# NewBee.net
KiCad netlist of a schematic drawn in Altium Designer
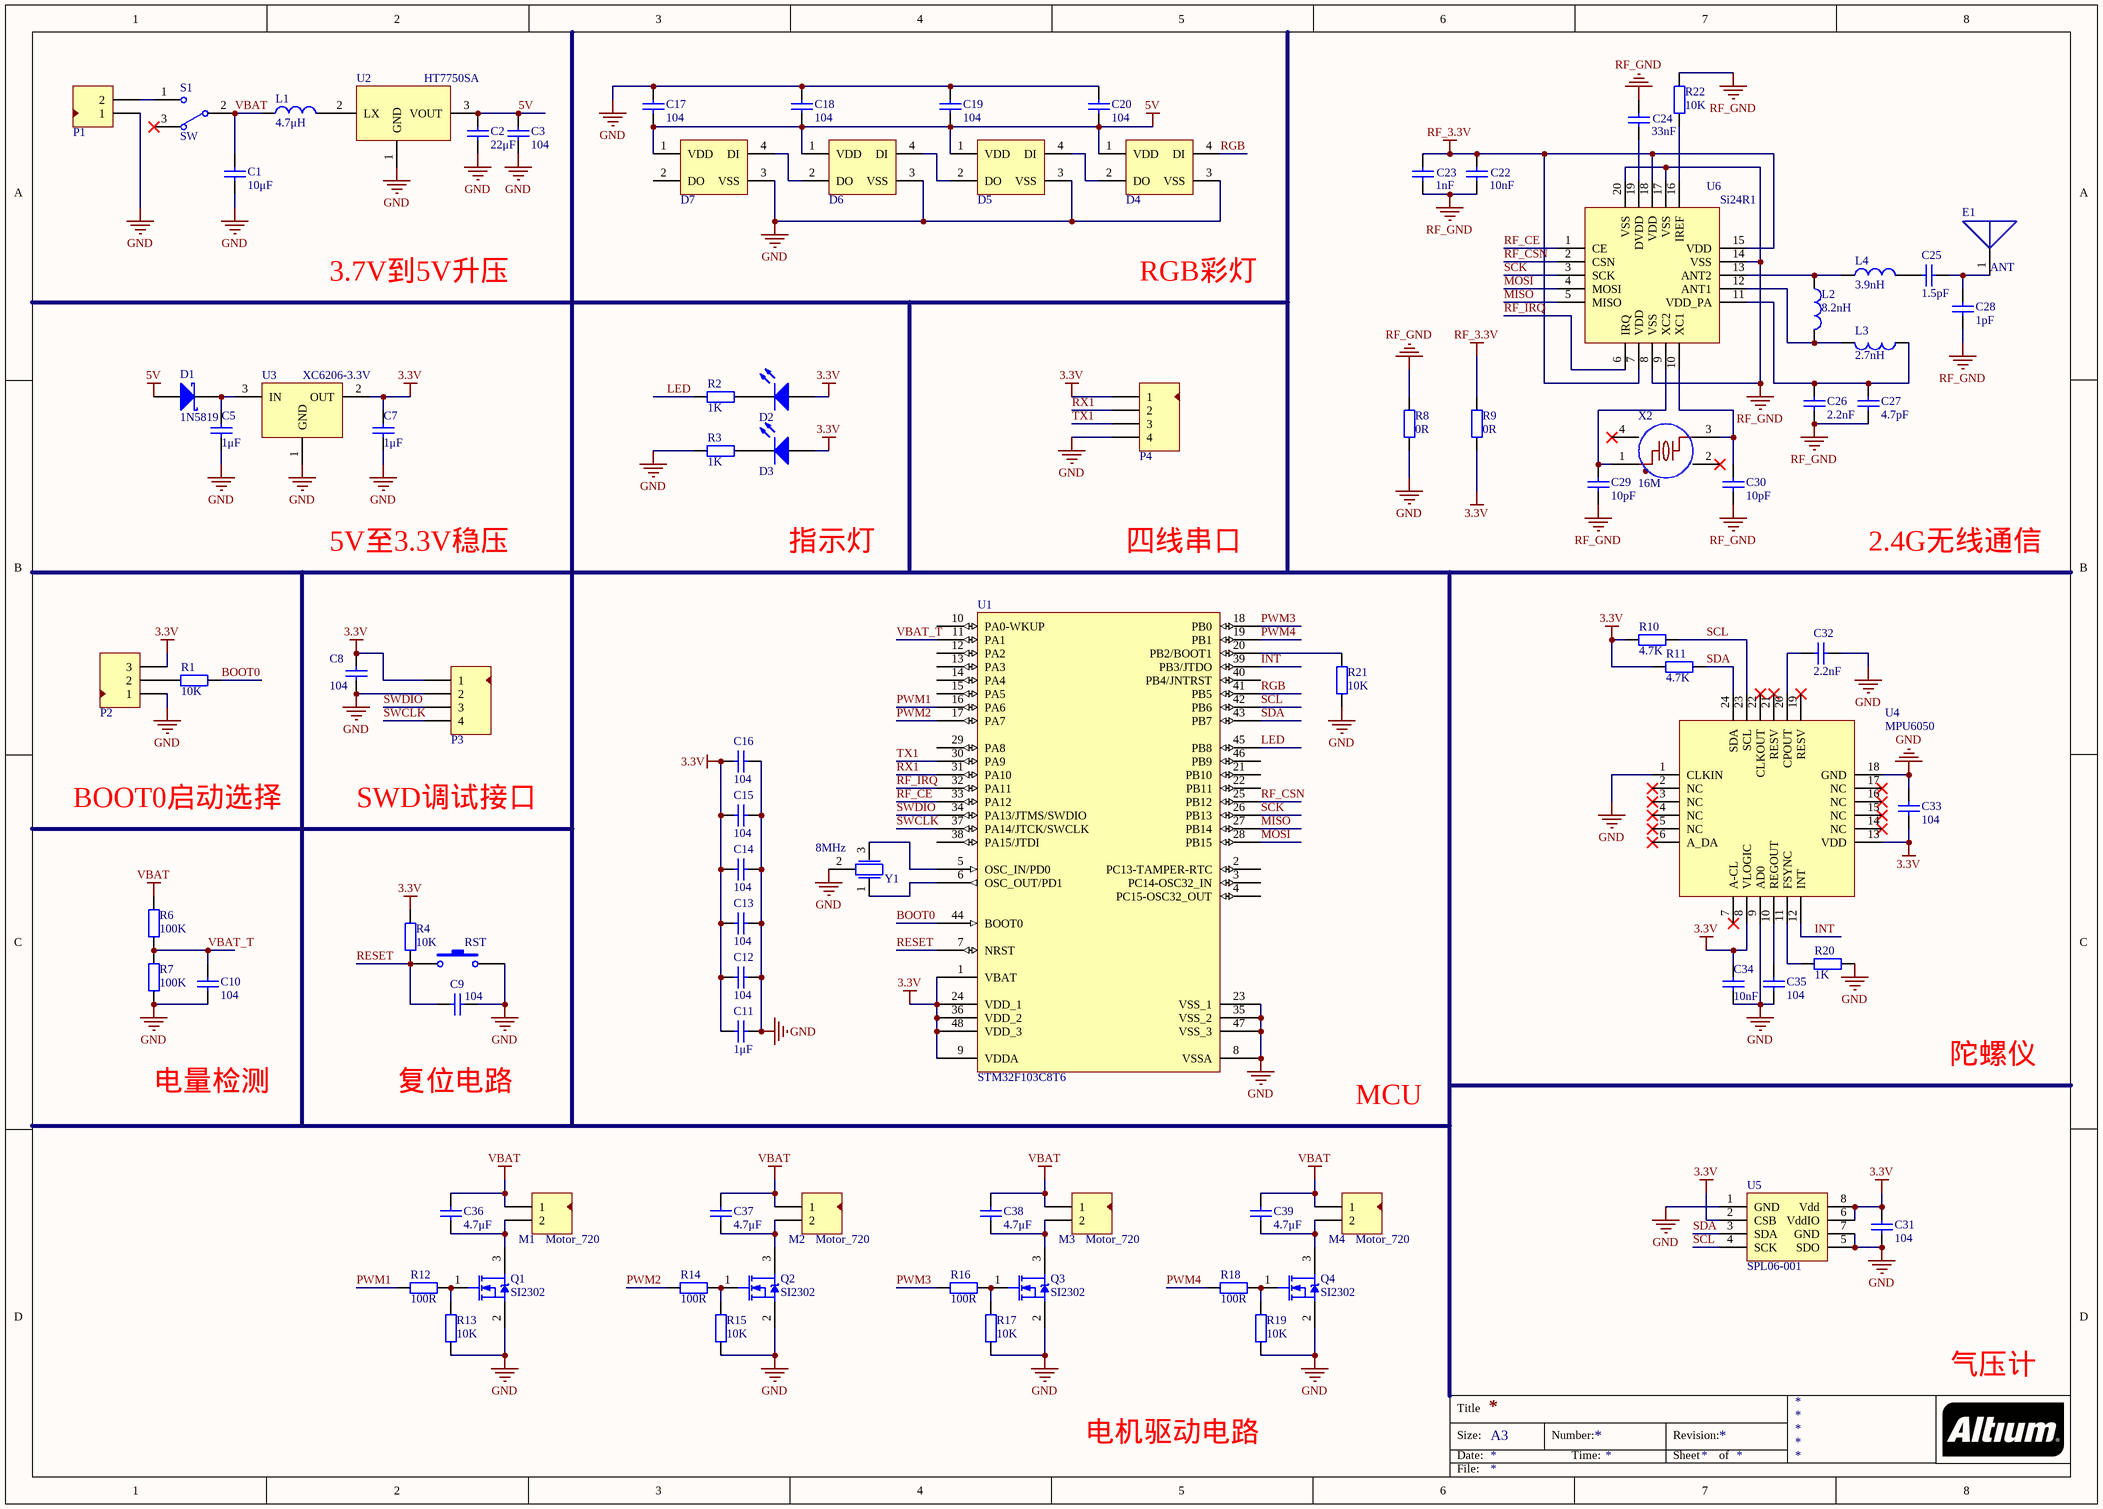
[diagram p0: NewBee.SchDoc]

(export (version "E")
  (design (tool "Eeschema 10.0.6"))
  (components
    (comp (ref "C1")
      (value "10μF")
      (footprint "C-0603")
      (description "贴片瓷片电容")
      (fields (field (name "PUBLISHER") "Altium Limited"))
      (libsource (lib "ChunLee") (part "Cap-S"))
    )
    (comp (ref "C2")
      (value "22μF")
      (footprint "C-0603")
      (description "贴片瓷片电容")
      (fields (field (name "PUBLISHER") "Altium Limited"))
      (libsource (lib "ChunLee") (part "Cap-S"))
    )
    (comp (ref "C3")
      (value "104")
      (footprint "C-0603")
      (description "贴片瓷片电容")
      (fields (field (name "PUBLISHER") "Altium Limited"))
      (libsource (lib "ChunLee") (part "Cap-S"))
    )
    (comp (ref "C5")
      (value "1μF")
      (footprint "C-0603")
      (description "贴片瓷片电容")
      (fields (field (name "PUBLISHER") "Altium Limited"))
      (libsource (lib "ChunLee") (part "Cap-S"))
    )
    (comp (ref "C7")
      (value "1μF")
      (footprint "C-0603")
      (description "贴片瓷片电容")
      (fields (field (name "PUBLISHER") "Altium Limited"))
      (libsource (lib "ChunLee") (part "Cap-S"))
    )
    (comp (ref "C8")
      (value "104")
      (footprint "C-0603")
      (description "贴片瓷片电容")
      (fields (field (name "PUBLISHER") "Altium Limited"))
      (libsource (lib "ChunLee") (part "Cap-S"))
    )
    (comp (ref "C9")
      (value "104")
      (footprint "C-0603")
      (description "贴片瓷片电容")
      (fields (field (name "PUBLISHER") "Altium Limited"))
      (libsource (lib "ChunLee") (part "Cap-S"))
    )
    (comp (ref "C10")
      (value "104")
      (footprint "C-0603")
      (description "贴片瓷片电容")
      (fields (field (name "PUBLISHER") "Altium Limited"))
      (libsource (lib "ChunLee") (part "Cap-S"))
    )
    (comp (ref "C11")
      (value "1μF")
      (footprint "C-0603")
      (description "贴片瓷片电容")
      (fields (field (name "PUBLISHER") "Altium Limited"))
      (libsource (lib "ChunLee") (part "Cap-S"))
    )
    (comp (ref "C12")
      (value "104")
      (footprint "C-0603")
      (description "贴片瓷片电容")
      (fields (field (name "PUBLISHER") "Altium Limited"))
      (libsource (lib "ChunLee") (part "Cap-S"))
    )
    (comp (ref "C13")
      (value "104")
      (footprint "C-0603")
      (description "贴片瓷片电容")
      (fields (field (name "PUBLISHER") "Altium Limited"))
      (libsource (lib "ChunLee") (part "Cap-S"))
    )
    (comp (ref "C14")
      (value "104")
      (footprint "C-0603")
      (description "贴片瓷片电容")
      (fields (field (name "PUBLISHER") "Altium Limited"))
      (libsource (lib "ChunLee") (part "Cap-S"))
    )
    (comp (ref "C15")
      (value "104")
      (footprint "C-0603")
      (description "贴片瓷片电容")
      (fields (field (name "PUBLISHER") "Altium Limited"))
      (libsource (lib "ChunLee") (part "Cap-S"))
    )
    (comp (ref "C16")
      (value "104")
      (footprint "C-0603")
      (description "贴片瓷片电容")
      (fields (field (name "PUBLISHER") "Altium Limited"))
      (libsource (lib "ChunLee") (part "Cap-S"))
    )
    (comp (ref "C17")
      (value "104")
      (footprint "C-0603")
      (description "贴片瓷片电容")
      (fields (field (name "PUBLISHER") "Altium Limited"))
      (libsource (lib "ChunLee") (part "Cap-S"))
    )
    (comp (ref "C18")
      (value "104")
      (footprint "C-0603")
      (description "贴片瓷片电容")
      (fields (field (name "PUBLISHER") "Altium Limited"))
      (libsource (lib "ChunLee") (part "Cap-S"))
    )
    (comp (ref "C19")
      (value "104")
      (footprint "C-0603")
      (description "贴片瓷片电容")
      (fields (field (name "PUBLISHER") "Altium Limited"))
      (libsource (lib "ChunLee") (part "Cap-S"))
    )
    (comp (ref "C20")
      (value "104")
      (footprint "C-0603")
      (description "贴片瓷片电容")
      (fields (field (name "PUBLISHER") "Altium Limited"))
      (libsource (lib "ChunLee") (part "Cap-S"))
    )
    (comp (ref "C22")
      (value "10nF")
      (footprint "C-0603")
      (description "贴片瓷片电容")
      (fields (field (name "PUBLISHER") "Altium Limited"))
      (libsource (lib "ChunLee") (part "Cap-S"))
    )
    (comp (ref "C23")
      (value "1nF")
      (footprint "C-0603")
      (description "贴片瓷片电容")
      (fields (field (name "PUBLISHER") "Altium Limited"))
      (libsource (lib "ChunLee") (part "Cap-S"))
    )
    (comp (ref "C24")
      (value "33nF")
      (footprint "C-0603")
      (description "贴片瓷片电容")
      (fields (field (name "PUBLISHER") "Altium Limited"))
      (libsource (lib "ChunLee") (part "Cap-S"))
    )
    (comp (ref "C25")
      (value "1.5pF")
      (footprint "C-0603")
      (description "贴片瓷片电容")
      (fields (field (name "PUBLISHER") "Altium Limited"))
      (libsource (lib "ChunLee") (part "Cap-S"))
    )
    (comp (ref "C26")
      (value "2.2nF")
      (footprint "C-0603")
      (description "贴片瓷片电容")
      (fields (field (name "PUBLISHER") "Altium Limited"))
      (libsource (lib "ChunLee") (part "Cap-S"))
    )
    (comp (ref "C27")
      (value "4.7pF")
      (footprint "C-0603")
      (description "贴片瓷片电容")
      (fields (field (name "PUBLISHER") "Altium Limited"))
      (libsource (lib "ChunLee") (part "Cap-S"))
    )
    (comp (ref "C28")
      (value "1pF")
      (footprint "C-0603")
      (description "贴片瓷片电容")
      (fields (field (name "PUBLISHER") "Altium Limited"))
      (libsource (lib "ChunLee") (part "Cap-S"))
    )
    (comp (ref "C29")
      (value "10pF")
      (footprint "C-0603")
      (description "贴片瓷片电容")
      (fields (field (name "PUBLISHER") "Altium Limited"))
      (libsource (lib "ChunLee") (part "Cap-S"))
    )
    (comp (ref "C30")
      (value "10pF")
      (footprint "C-0603")
      (description "贴片瓷片电容")
      (fields (field (name "PUBLISHER") "Altium Limited"))
      (libsource (lib "ChunLee") (part "Cap-S"))
    )
    (comp (ref "C31")
      (value "104")
      (footprint "C-0603")
      (description "贴片瓷片电容")
      (fields (field (name "PUBLISHER") "Altium Limited"))
      (libsource (lib "ChunLee") (part "Cap-S"))
    )
    (comp (ref "C32")
      (value "2.2nF")
      (footprint "C-0603")
      (description "贴片瓷片电容")
      (fields (field (name "PUBLISHER") "Altium Limited"))
      (libsource (lib "ChunLee") (part "Cap-S"))
    )
    (comp (ref "C33")
      (value "104")
      (footprint "C-0603")
      (description "贴片瓷片电容")
      (fields (field (name "PUBLISHER") "Altium Limited"))
      (libsource (lib "ChunLee") (part "Cap-S"))
    )
    (comp (ref "C34")
      (value "10nF")
      (footprint "C-0603")
      (description "贴片瓷片电容")
      (fields (field (name "PUBLISHER") "Altium Limited"))
      (libsource (lib "ChunLee") (part "Cap-S"))
    )
    (comp (ref "C35")
      (value "104")
      (footprint "C-0603")
      (description "贴片瓷片电容")
      (fields (field (name "PUBLISHER") "Altium Limited"))
      (libsource (lib "ChunLee") (part "Cap-S"))
    )
    (comp (ref "C36")
      (value "4.7μF")
      (footprint "C-0603")
      (description "贴片瓷片电容")
      (fields (field (name "PUBLISHER") "Altium Limited"))
      (libsource (lib "ChunLee") (part "Cap-S"))
    )
    (comp (ref "C37")
      (value "4.7μF")
      (footprint "C-0603")
      (description "贴片瓷片电容")
      (fields (field (name "PUBLISHER") "Altium Limited"))
      (libsource (lib "ChunLee") (part "Cap-S"))
    )
    (comp (ref "C38")
      (value "4.7μF")
      (footprint "C-0603")
      (description "贴片瓷片电容")
      (fields (field (name "PUBLISHER") "Altium Limited"))
      (libsource (lib "ChunLee") (part "Cap-S"))
    )
    (comp (ref "C39")
      (value "4.7μF")
      (footprint "C-0603")
      (description "贴片瓷片电容")
      (fields (field (name "PUBLISHER") "Altium Limited"))
      (libsource (lib "ChunLee") (part "Cap-S"))
    )
    (comp (ref "D1")
      (value "1N5819")
      (footprint "SOD-323_L1.6-W1.3-LS2.7-RD")
      (description "肖特基二极管")
      (fields (field (name "TYPE") "1N5819") (field (name "PUBLISHER") "Altium Limited"))
      (libsource (lib "ChunLee") (part "Diode-Schottky"))
    )
    (comp (ref "D2")
      (value "LED0")
      (footprint "LED-0805")
      (description "发光二极管")
      (fields (field (name "PUBLISHER") "Altium Limited"))
      (libsource (lib "ChunLee") (part "LED0"))
    )
    (comp (ref "D3")
      (value "LED0")
      (footprint "LED-0805")
      (description "发光二极管")
      (fields (field (name "PUBLISHER") "Altium Limited"))
      (libsource (lib "ChunLee") (part "LED0"))
    )
    (comp (ref "D4")
      (value "WS2812B")
      (footprint "SMD-5050-4")
      (description "WS2812B 4脚RGB全彩LED")
      (libsource (lib "ChunLee") (part "WS2812B"))
    )
    (comp (ref "D5")
      (value "WS2812B")
      (footprint "SMD-5050-4")
      (description "WS2812B 4脚RGB全彩LED")
      (libsource (lib "ChunLee") (part "WS2812B"))
    )
    (comp (ref "D6")
      (value "WS2812B")
      (footprint "SMD-5050-4")
      (description "WS2812B 4脚RGB全彩LED")
      (libsource (lib "ChunLee") (part "WS2812B"))
    )
    (comp (ref "D7")
      (value "WS2812B")
      (footprint "SMD-5050-4")
      (description "WS2812B 4脚RGB全彩LED")
      (libsource (lib "ChunLee") (part "WS2812B"))
    )
    (comp (ref "E1")
      (value "ANT")
      (footprint "NewBee_PcbLib:AN3216")
      (description "2.4G Antenna")
      (fields (field (name "PUBLISHER") "mazhongwei"))
      (libsource (lib "NewBee_Schlib") (part "ANT"))
    )
    (comp (ref "L1")
      (value "4.7μH")
      (footprint "1210")
      (description "电感")
      (fields (field (name "Comment") "Inductor") (field (name "PUBLISHER") "Altium Limited"))
      (libsource (lib "ChunLee") (part "Inductor"))
    )
    (comp (ref "L2")
      (value "8.2nH")
      (footprint "0603-1")
      (description "电感")
      (fields (field (name "Comment") "Inductor") (field (name "PUBLISHER") "Altium Limited"))
      (libsource (lib "ChunLee") (part "Inductor"))
    )
    (comp (ref "L3")
      (value "2.7nH")
      (footprint "0603-1")
      (description "电感")
      (fields (field (name "Comment") "Inductor") (field (name "PUBLISHER") "Altium Limited"))
      (libsource (lib "ChunLee") (part "Inductor"))
    )
    (comp (ref "L4")
      (value "3.9nH")
      (footprint "0603-1")
      (description "电感")
      (fields (field (name "Comment") "Inductor") (field (name "PUBLISHER") "Altium Limited"))
      (libsource (lib "ChunLee") (part "Inductor"))
    )
    (comp (ref "M1")
      (value "Motor_720")
      (footprint "PH2.0-2P-TH")
      (description "接插件")
      (fields (field (name "PUBLISHER") "Altium Limited"))
      (libsource (lib "HDR_ChunLee") (part "Header 2"))
    )
    (comp (ref "M2")
      (value "Motor_720")
      (footprint "PH2.0-2P-TH")
      (description "接插件")
      (fields (field (name "PUBLISHER") "Altium Limited"))
      (libsource (lib "HDR_ChunLee") (part "Header 2"))
    )
    (comp (ref "M3")
      (value "Motor_720")
      (footprint "PH2.0-2P-TH")
      (description "接插件")
      (fields (field (name "PUBLISHER") "Altium Limited"))
      (libsource (lib "HDR_ChunLee") (part "Header 2"))
    )
    (comp (ref "M4")
      (value "Motor_720")
      (footprint "PH2.0-2P-TH")
      (description "接插件")
      (fields (field (name "PUBLISHER") "Altium Limited"))
      (libsource (lib "HDR_ChunLee") (part "Header 2"))
    )
    (comp (ref "P1")
      (value "Header 2")
      (footprint "PH2.0-2P-SMD-WT")
      (description "接插件")
      (fields (field (name "PUBLISHER") "Altium Limited"))
      (libsource (lib "") (part "Header 2_1"))
    )
    (comp (ref "P2")
      (value "Header 3")
      (footprint "HDR3X1-2.54")
      (description "接插件")
      (fields (field (name "PUBLISHER") "Altium Limited"))
      (libsource (lib "HDR_ChunLee") (part "Header 3"))
    )
    (comp (ref "P3")
      (value "Header 4")
      (footprint "HDR4X1-2.54")
      (description "接插件")
      (fields (field (name "PUBLISHER") "Altium Limited"))
      (libsource (lib "HDR_ChunLee") (part "Header 4"))
    )
    (comp (ref "P4")
      (value "Header 4")
      (footprint "HDR4X1-2.54")
      (description "接插件")
      (fields (field (name "PUBLISHER") "Altium Limited"))
      (libsource (lib "HDR_ChunLee") (part "Header 4"))
    )
    (comp (ref "Q1")
      (value "SI2302")
      (footprint "SOT23-3")
      (description "N沟道贴片")
      (fields (field (name "PUBLISHER") "Altium Limited"))
      (libsource (lib "ChunLee") (part "SI2302"))
    )
    (comp (ref "Q2")
      (value "SI2302")
      (footprint "SOT23-3")
      (description "N沟道贴片")
      (fields (field (name "PUBLISHER") "Altium Limited"))
      (libsource (lib "ChunLee") (part "SI2302"))
    )
    (comp (ref "Q3")
      (value "SI2302")
      (footprint "SOT23-3")
      (description "N沟道贴片")
      (fields (field (name "PUBLISHER") "Altium Limited"))
      (libsource (lib "ChunLee") (part "SI2302"))
    )
    (comp (ref "Q4")
      (value "SI2302")
      (footprint "SOT23-3")
      (description "N沟道贴片")
      (fields (field (name "PUBLISHER") "Altium Limited"))
      (libsource (lib "ChunLee") (part "SI2302"))
    )
    (comp (ref "R1")
      (value "10K")
      (footprint "0603-1")
      (description "贴片电阻")
      (fields (field (name "PUBLISHER") "Altium Limited"))
      (libsource (lib "") (part "Res1_3"))
    )
    (comp (ref "R2")
      (value "1K")
      (footprint "0603-1")
      (description "贴片电阻")
      (fields (field (name "PUBLISHER") "Altium Limited"))
      (libsource (lib "") (part "Res1_2"))
    )
    (comp (ref "R3")
      (value "1K")
      (footprint "0603-1")
      (description "贴片电阻")
      (fields (field (name "PUBLISHER") "Altium Limited"))
      (libsource (lib "") (part "Res1_2"))
    )
    (comp (ref "R4")
      (value "10K")
      (footprint "0603-1")
      (description "贴片电阻")
      (fields (field (name "PUBLISHER") "Altium Limited"))
      (libsource (lib "") (part "Res1_1"))
    )
    (comp (ref "R6")
      (value "100K")
      (footprint "0603-1")
      (description "贴片电阻")
      (fields (field (name "PUBLISHER") "Altium Limited"))
      (libsource (lib "ChunLee") (part "Res1"))
    )
    (comp (ref "R7")
      (value "100K")
      (footprint "0603-1")
      (description "贴片电阻")
      (fields (field (name "PUBLISHER") "Altium Limited"))
      (libsource (lib "ChunLee") (part "Res1"))
    )
    (comp (ref "R8")
      (value "0R")
      (footprint "0603-1")
      (description "贴片电阻")
      (fields (field (name "PUBLISHER") "Altium Limited"))
      (libsource (lib "ChunLee") (part "Res1"))
    )
    (comp (ref "R9")
      (value "0R")
      (footprint "0603-1")
      (description "贴片电阻")
      (fields (field (name "PUBLISHER") "Altium Limited"))
      (libsource (lib "ChunLee") (part "Res1"))
    )
    (comp (ref "R10")
      (value "4.7K")
      (footprint "0603-1")
      (description "贴片电阻")
      (fields (field (name "PUBLISHER") "Altium Limited"))
      (libsource (lib "") (part "Res1_2"))
    )
    (comp (ref "R11")
      (value "4.7K")
      (footprint "0603-1")
      (description "贴片电阻")
      (fields (field (name "PUBLISHER") "Altium Limited"))
      (libsource (lib "") (part "Res1_2"))
    )
    (comp (ref "R12")
      (value "100R")
      (footprint "0603-1")
      (description "贴片电阻")
      (fields (field (name "PUBLISHER") "Altium Limited"))
      (libsource (lib "") (part "Res1_2"))
    )
    (comp (ref "R13")
      (value "10K")
      (footprint "0603-1")
      (description "贴片电阻")
      (fields (field (name "PUBLISHER") "Altium Limited"))
      (libsource (lib "") (part "Res1_1"))
    )
    (comp (ref "R14")
      (value "100R")
      (footprint "0603-1")
      (description "贴片电阻")
      (fields (field (name "PUBLISHER") "Altium Limited"))
      (libsource (lib "") (part "Res1_2"))
    )
    (comp (ref "R15")
      (value "10K")
      (footprint "0603-1")
      (description "贴片电阻")
      (fields (field (name "PUBLISHER") "Altium Limited"))
      (libsource (lib "") (part "Res1_1"))
    )
    (comp (ref "R16")
      (value "100R")
      (footprint "0603-1")
      (description "贴片电阻")
      (fields (field (name "PUBLISHER") "Altium Limited"))
      (libsource (lib "") (part "Res1_2"))
    )
    (comp (ref "R17")
      (value "10K")
      (footprint "0603-1")
      (description "贴片电阻")
      (fields (field (name "PUBLISHER") "Altium Limited"))
      (libsource (lib "") (part "Res1_1"))
    )
    (comp (ref "R18")
      (value "100R")
      (footprint "0603-1")
      (description "贴片电阻")
      (fields (field (name "PUBLISHER") "Altium Limited"))
      (libsource (lib "") (part "Res1_2"))
    )
    (comp (ref "R19")
      (value "10K")
      (footprint "0603-1")
      (description "贴片电阻")
      (fields (field (name "PUBLISHER") "Altium Limited"))
      (libsource (lib "") (part "Res1_1"))
    )
    (comp (ref "R20")
      (value "1K")
      (footprint "0603-1")
      (description "贴片电阻")
      (fields (field (name "PUBLISHER") "Altium Limited"))
      (libsource (lib "") (part "Res1_3"))
    )
    (comp (ref "R21")
      (value "10K")
      (footprint "0603-1")
      (description "贴片电阻")
      (fields (field (name "PUBLISHER") "Altium Limited"))
      (libsource (lib "ChunLee") (part "Res1"))
    )
    (comp (ref "R22")
      (value "10K")
      (footprint "0603-1")
      (description "贴片电阻")
      (fields (field (name "PUBLISHER") "Altium Limited"))
      (libsource (lib "ChunLee") (part "Res1"))
    )
    (comp (ref "RST")
      (value "SW-PB")
      (footprint "SW-SMD_L4.0-W3.0-P4.8-LS5.0-L")
      (description "微动开关")
      (fields (field (name "PUBLISHER") "Altium Limited"))
      (libsource (lib "ChunLee") (part "SW-PB"))
    )
    (comp (ref "S1")
      (value "SW")
      (footprint "SW-SMD_DEALON_MK-12D04-G2")
      (description "开关")
      (fields (field (name "PUBLISHER") "Altium Limited"))
      (libsource (lib "ChunLee") (part "SW-SPDT"))
    )
    (comp (ref "U1")
      (value "STM32F103C8T6")
      (footprint "LQFP-48")
      (description "STM32F103, 48引脚, 64Kb Flash, 20Kb SRAM")
      (fields (field (name "PUBLISHER") "Altium Limited"))
      (libsource (lib "ChunLee") (part "STM32F103C8T6"))
    )
    (comp (ref "U2")
      (value "HT7750SA")
      (footprint "SOT23-3")
      (libsource (lib "ChunLee") (part "HT7750SA_3pins"))
    )
    (comp (ref "U3")
      (value "XC6206-3.3V")
      (footprint "SOT23-3")
      (description "稳压芯片")
      (libsource (lib "ChunLee") (part "XC6206"))
    )
    (comp (ref "U4") (value "MPU6050") (footprint "QFN-24") (libsource (lib "ChunLee") (part "MPU6050")))
    (comp (ref "U5")
      (value "SPL06-001")
      (footprint "SENSOR-SMD_SPL06-001")
      (description "气压计")
      (fields (field (name "PUBLISHER") "mazhongwei"))
      (libsource (lib "NewBee_Schlib") (part "FBM320"))
    )
    (comp (ref "U6") (value "Si24R1") (footprint "QFN20") (libsource (lib "NewBee_Schlib") (part "nRF24L01")))
    (comp (ref "X2")
      (value "16M")
      (footprint "X-SMD_4P-L3.2-W2.5-BL")
      (libsource (lib "ChunLee") (part "XTAL-4PIN"))
    )
    (comp (ref "Y1")
      (value "8MHz")
      (footprint "OSC-SMD_3P-L3.2-W1.3-P1.20-L")
      (description "贴片晶振")
      (libsource (lib "ChunLee") (part "XTAL-3PIN"))
    )
  )
  (nets
    (net (code "1") (name "/BOOT0") (class "Default")
      (node (ref "R1") (pin "1") (pinfunction "1_1") (pintype "passive"))
      (node (ref "U1") (pin "44") (pinfunction "BOOT0_44") (pintype "input"))
    )
    (net (code "2") (name "/INT") (class "Default")
      (node (ref "U1") (pin "39") (pinfunction "PB3/JTDO_39") (pintype "bidirectional"))
      (node (ref "U4") (pin "12") (pinfunction "INT_12") (pintype "passive"))
    )
    (net (code "3") (name "/LED") (class "Default")
      (node (ref "R2") (pin "1") (pinfunction "1_1") (pintype "passive"))
      (node (ref "U1") (pin "45") (pinfunction "PB8_45") (pintype "bidirectional"))
    )
    (net (code "4") (name "/MISO") (class "Default")
      (node (ref "U1") (pin "27") (pinfunction "PB14_27") (pintype "bidirectional"))
      (node (ref "U6") (pin "5") (pinfunction "MISO_5") (pintype "passive"))
    )
    (net (code "5") (name "/MOSI") (class "Default")
      (node (ref "U1") (pin "28") (pinfunction "PB15_28") (pintype "bidirectional"))
      (node (ref "U6") (pin "4") (pinfunction "MOSI_4") (pintype "passive"))
    )
    (net (code "6") (name "/PWM1") (class "Default")
      (node (ref "R12") (pin "1") (pinfunction "1_1") (pintype "passive"))
      (node (ref "U1") (pin "16") (pinfunction "PA6_16") (pintype "bidirectional"))
    )
    (net (code "7") (name "/PWM2") (class "Default")
      (node (ref "R14") (pin "1") (pinfunction "1_1") (pintype "passive"))
      (node (ref "U1") (pin "17") (pinfunction "PA7_17") (pintype "bidirectional"))
    )
    (net (code "8") (name "/PWM3") (class "Default")
      (node (ref "R16") (pin "1") (pinfunction "1_1") (pintype "passive"))
      (node (ref "U1") (pin "18") (pinfunction "PB0_18") (pintype "bidirectional"))
    )
    (net (code "9") (name "/PWM4") (class "Default")
      (node (ref "R18") (pin "1") (pinfunction "1_1") (pintype "passive"))
      (node (ref "U1") (pin "19") (pinfunction "PB1_19") (pintype "bidirectional"))
    )
    (net (code "10") (name "/RESET") (class "Default")
      (node (ref "C9") (pin "1") (pinfunction "1_1") (pintype "passive"))
      (node (ref "R4") (pin "1") (pinfunction "1_1") (pintype "passive"))
      (node (ref "RST") (pin "1") (pinfunction "1_1") (pintype "passive"))
      (node (ref "U1") (pin "7") (pinfunction "NRST_7") (pintype "bidirectional"))
    )
    (net (code "11") (name "/RF_CE") (class "Default")
      (node (ref "U1") (pin "33") (pinfunction "PA12_33") (pintype "bidirectional"))
      (node (ref "U6") (pin "1") (pinfunction "CE_1") (pintype "passive"))
    )
    (net (code "12") (name "/RF_CSN") (class "Default")
      (node (ref "U1") (pin "25") (pinfunction "PB12_25") (pintype "bidirectional"))
      (node (ref "U6") (pin "2") (pinfunction "CSN_2") (pintype "passive"))
    )
    (net (code "13") (name "/RF_IRQ") (class "Default")
      (node (ref "U1") (pin "32") (pinfunction "PA11_32") (pintype "bidirectional"))
      (node (ref "U6") (pin "6") (pinfunction "IRQ_6") (pintype "passive"))
    )
    (net (code "14") (name "/RGB") (class "Default")
      (node (ref "D4") (pin "4") (pinfunction "DI_4") (pintype "passive"))
      (node (ref "U1") (pin "41") (pinfunction "PB5_41") (pintype "bidirectional"))
    )
    (net (code "15") (name "/RX1") (class "Default")
      (node (ref "P4") (pin "2") (pinfunction "2_2") (pintype "passive"))
      (node (ref "U1") (pin "31") (pinfunction "PA10_31") (pintype "bidirectional"))
    )
    (net (code "16") (name "/SCK") (class "Default")
      (node (ref "U1") (pin "26") (pinfunction "PB13_26") (pintype "bidirectional"))
      (node (ref "U6") (pin "3") (pinfunction "SCK_3") (pintype "passive"))
    )
    (net (code "17") (name "/SCL") (class "Default")
      (node (ref "R10") (pin "2") (pinfunction "2_2") (pintype "passive"))
      (node (ref "U1") (pin "42") (pinfunction "PB6_42") (pintype "bidirectional"))
      (node (ref "U4") (pin "23") (pinfunction "SCL_23") (pintype "passive"))
      (node (ref "U5") (pin "4") (pinfunction "SCK_4") (pintype "passive"))
    )
    (net (code "18") (name "/SDA") (class "Default")
      (node (ref "R11") (pin "2") (pinfunction "2_2") (pintype "passive"))
      (node (ref "U1") (pin "43") (pinfunction "PB7_43") (pintype "bidirectional"))
      (node (ref "U4") (pin "24") (pinfunction "SDA_24") (pintype "passive"))
      (node (ref "U5") (pin "3") (pinfunction "SDA_3") (pintype "passive"))
    )
    (net (code "19") (name "/SWCLK") (class "Default")
      (node (ref "P3") (pin "4") (pinfunction "4_4") (pintype "passive"))
      (node (ref "U1") (pin "37") (pinfunction "PA14/JTCK/SWCLK_37") (pintype "bidirectional"))
    )
    (net (code "20") (name "/SWDIO") (class "Default")
      (node (ref "P3") (pin "3") (pinfunction "3_3") (pintype "passive"))
      (node (ref "U1") (pin "34") (pinfunction "PA13/JTMS/SWDIO_34") (pintype "bidirectional"))
    )
    (net (code "21") (name "/TX1") (class "Default")
      (node (ref "P4") (pin "3") (pinfunction "3_3") (pintype "passive"))
      (node (ref "U1") (pin "30") (pinfunction "PA9_30") (pintype "bidirectional"))
    )
    (net (code "22") (name "/VBAT_T") (class "Default")
      (node (ref "C10") (pin "2") (pinfunction "2_2") (pintype "passive"))
      (node (ref "R6") (pin "2") (pinfunction "2_2") (pintype "passive"))
      (node (ref "R7") (pin "1") (pinfunction "1_1") (pintype "passive"))
      (node (ref "U1") (pin "11") (pinfunction "PA1_11") (pintype "bidirectional"))
    )
    (net (code "23") (name "3.3V") (class "Default")
      (node (ref "C11") (pin "2") (pinfunction "2_2") (pintype "passive"))
      (node (ref "C12") (pin "2") (pinfunction "2_2") (pintype "passive"))
      (node (ref "C13") (pin "2") (pinfunction "2_2") (pintype "passive"))
      (node (ref "C14") (pin "1") (pinfunction "1_1") (pintype "passive"))
      (node (ref "C15") (pin "2") (pinfunction "2_2") (pintype "passive"))
      (node (ref "C16") (pin "2") (pinfunction "2_2") (pintype "passive"))
      (node (ref "C31") (pin "2") (pinfunction "2_2") (pintype "passive"))
      (node (ref "C33") (pin "2") (pinfunction "2_2") (pintype "passive"))
      (node (ref "C34") (pin "2") (pinfunction "2_2") (pintype "passive"))
      (node (ref "C7") (pin "1") (pinfunction "1_1") (pintype "passive"))
      (node (ref "C8") (pin "1") (pinfunction "1_1") (pintype "passive"))
      (node (ref "D2") (pin "1") (pinfunction "A_1") (pintype "passive"))
      (node (ref "D3") (pin "1") (pinfunction "A_1") (pintype "passive"))
      (node (ref "P2") (pin "3") (pinfunction "3_3") (pintype "passive"))
      (node (ref "P3") (pin "1") (pinfunction "1_1") (pintype "passive"))
      (node (ref "P4") (pin "1") (pinfunction "1_1") (pintype "passive"))
      (node (ref "R10") (pin "1") (pinfunction "1_1") (pintype "passive"))
      (node (ref "R11") (pin "1") (pinfunction "1_1") (pintype "passive"))
      (node (ref "R4") (pin "2") (pinfunction "2_2") (pintype "passive"))
      (node (ref "R9") (pin "2") (pinfunction "2_2") (pintype "passive"))
      (node (ref "U1") (pin "1") (pinfunction "VBAT_1") (pintype "power_in"))
      (node (ref "U1") (pin "24") (pinfunction "VDD_1_24") (pintype "power_in"))
      (node (ref "U1") (pin "36") (pinfunction "VDD_2_36") (pintype "power_in"))
      (node (ref "U1") (pin "48") (pinfunction "VDD_3_48") (pintype "power_in"))
      (node (ref "U1") (pin "9") (pinfunction "VDDA_9") (pintype "power_in"))
      (node (ref "U3") (pin "2") (pinfunction "OUT_2") (pintype "passive"))
      (node (ref "U4") (pin "13") (pinfunction "VDD_13") (pintype "passive"))
      (node (ref "U4") (pin "8") (pinfunction "VLOGIC_8") (pintype "passive"))
      (node (ref "U5") (pin "2") (pinfunction "CSB_2") (pintype "passive"))
      (node (ref "U5") (pin "6") (pinfunction "VddIO_6") (pintype "passive"))
      (node (ref "U5") (pin "8") (pinfunction "Vdd_8") (pintype "passive"))
    )
    (net (code "24") (name "5V") (class "Default")
      (node (ref "C17") (pin "1") (pinfunction "1_1") (pintype "passive"))
      (node (ref "C18") (pin "1") (pinfunction "1_1") (pintype "passive"))
      (node (ref "C19") (pin "1") (pinfunction "1_1") (pintype "passive"))
      (node (ref "C2") (pin "2") (pinfunction "2_2") (pintype "passive"))
      (node (ref "C20") (pin "1") (pinfunction "1_1") (pintype "passive"))
      (node (ref "C3") (pin "2") (pinfunction "2_2") (pintype "passive"))
      (node (ref "D1") (pin "1") (pinfunction "A_1") (pintype "passive"))
      (node (ref "D4") (pin "1") (pinfunction "VDD_1") (pintype "passive"))
      (node (ref "D5") (pin "1") (pinfunction "VDD_1") (pintype "passive"))
      (node (ref "D6") (pin "1") (pinfunction "VDD_1") (pintype "passive"))
      (node (ref "D7") (pin "1") (pinfunction "VDD_1") (pintype "passive"))
      (node (ref "U2") (pin "3") (pinfunction "VOUT_3") (pintype "passive"))
    )
    (net (code "25") (name "GND") (class "Default")
      (node (ref "C1") (pin "1") (pinfunction "1_1") (pintype "passive"))
      (node (ref "C10") (pin "1") (pinfunction "1_1") (pintype "passive"))
      (node (ref "C11") (pin "1") (pinfunction "1_1") (pintype "passive"))
      (node (ref "C12") (pin "1") (pinfunction "1_1") (pintype "passive"))
      (node (ref "C13") (pin "1") (pinfunction "1_1") (pintype "passive"))
      (node (ref "C14") (pin "2") (pinfunction "2_2") (pintype "passive"))
      (node (ref "C15") (pin "1") (pinfunction "1_1") (pintype "passive"))
      (node (ref "C16") (pin "1") (pinfunction "1_1") (pintype "passive"))
      (node (ref "C17") (pin "2") (pinfunction "2_2") (pintype "passive"))
      (node (ref "C18") (pin "2") (pinfunction "2_2") (pintype "passive"))
      (node (ref "C19") (pin "2") (pinfunction "2_2") (pintype "passive"))
      (node (ref "C2") (pin "1") (pinfunction "1_1") (pintype "passive"))
      (node (ref "C20") (pin "2") (pinfunction "2_2") (pintype "passive"))
      (node (ref "C3") (pin "1") (pinfunction "1_1") (pintype "passive"))
      (node (ref "C31") (pin "1") (pinfunction "1_1") (pintype "passive"))
      (node (ref "C32") (pin "1") (pinfunction "1_1") (pintype "passive"))
      (node (ref "C33") (pin "1") (pinfunction "1_1") (pintype "passive"))
      (node (ref "C34") (pin "1") (pinfunction "1_1") (pintype "passive"))
      (node (ref "C35") (pin "2") (pinfunction "2_2") (pintype "passive"))
      (node (ref "C5") (pin "2") (pinfunction "2_2") (pintype "passive"))
      (node (ref "C7") (pin "2") (pinfunction "2_2") (pintype "passive"))
      (node (ref "C8") (pin "2") (pinfunction "2_2") (pintype "passive"))
      (node (ref "C9") (pin "2") (pinfunction "2_2") (pintype "passive"))
      (node (ref "D4") (pin "3") (pinfunction "VSS_3") (pintype "passive"))
      (node (ref "D5") (pin "3") (pinfunction "VSS_3") (pintype "passive"))
      (node (ref "D6") (pin "3") (pinfunction "VSS_3") (pintype "passive"))
      (node (ref "D7") (pin "3") (pinfunction "VSS_3") (pintype "passive"))
      (node (ref "P1") (pin "1") (pinfunction "1_1") (pintype "passive"))
      (node (ref "P2") (pin "1") (pinfunction "1_1") (pintype "passive"))
      (node (ref "P3") (pin "2") (pinfunction "2_2") (pintype "passive"))
      (node (ref "P4") (pin "4") (pinfunction "4_4") (pintype "passive"))
      (node (ref "Q1") (pin "2") (pinfunction "S_2") (pintype "passive"))
      (node (ref "Q2") (pin "2") (pinfunction "S_2") (pintype "passive"))
      (node (ref "Q3") (pin "2") (pinfunction "S_2") (pintype "passive"))
      (node (ref "Q4") (pin "2") (pinfunction "S_2") (pintype "passive"))
      (node (ref "R13") (pin "1") (pinfunction "1_1") (pintype "passive"))
      (node (ref "R15") (pin "1") (pinfunction "1_1") (pintype "passive"))
      (node (ref "R17") (pin "1") (pinfunction "1_1") (pintype "passive"))
      (node (ref "R19") (pin "1") (pinfunction "1_1") (pintype "passive"))
      (node (ref "R20") (pin "1") (pinfunction "1_1") (pintype "passive"))
      (node (ref "R21") (pin "2") (pinfunction "2_2") (pintype "passive"))
      (node (ref "R3") (pin "1") (pinfunction "1_1") (pintype "passive"))
      (node (ref "R7") (pin "2") (pinfunction "2_2") (pintype "passive"))
      (node (ref "R8") (pin "2") (pinfunction "2_2") (pintype "passive"))
      (node (ref "RST") (pin "2") (pinfunction "2_2") (pintype "passive"))
      (node (ref "U1") (pin "23") (pinfunction "VSS_1_23") (pintype "power_in"))
      (node (ref "U1") (pin "35") (pinfunction "VSS_2_35") (pintype "power_in"))
      (node (ref "U1") (pin "47") (pinfunction "VSS_3_47") (pintype "power_in"))
      (node (ref "U1") (pin "8") (pinfunction "VSSA_8") (pintype "power_in"))
      (node (ref "U2") (pin "1") (pinfunction "GND_1") (pintype "passive"))
      (node (ref "U3") (pin "1") (pinfunction "GND_1") (pintype "passive"))
      (node (ref "U4") (pin "1") (pinfunction "CLKIN_1") (pintype "passive"))
      (node (ref "U4") (pin "18") (pinfunction "GND_18") (pintype "passive"))
      (node (ref "U4") (pin "9") (pinfunction "AD0_9") (pintype "passive"))
      (node (ref "U5") (pin "1") (pinfunction "GND_1") (pintype "passive"))
      (node (ref "U5") (pin "5") (pinfunction "SDO_5") (pintype "passive"))
      (node (ref "U5") (pin "7") (pinfunction "GND_7") (pintype "passive"))
      (node (ref "Y1") (pin "2") (pinfunction "2_2") (pintype "passive"))
    )
    (net (code "26") (name "Net-(C25-Pad1)") (class "Default")
      (node (ref "C25") (pin "1") (pinfunction "1_1") (pintype "passive"))
      (node (ref "C28") (pin "2") (pinfunction "2_2") (pintype "passive"))
      (node (ref "E1") (pin "1") (pinfunction "1_1") (pintype "passive"))
    )
    (net (code "27") (name "Net-(C25-Pad2)") (class "Default")
      (node (ref "C25") (pin "2") (pinfunction "2_2") (pintype "passive"))
      (node (ref "L4") (pin "2") (pinfunction "2_2") (pintype "passive"))
    )
    (net (code "28") (name "Net-(D1-K)") (class "Default")
      (node (ref "C5") (pin "1") (pinfunction "1_1") (pintype "passive"))
      (node (ref "D1") (pin "2") (pinfunction "K_2") (pintype "passive"))
      (node (ref "U3") (pin "3") (pinfunction "IN_3") (pintype "passive"))
    )
    (net (code "29") (name "Net-(D2-K)") (class "Default")
      (node (ref "D2") (pin "2") (pinfunction "K_2") (pintype "passive"))
      (node (ref "R2") (pin "2") (pinfunction "2_2") (pintype "passive"))
    )
    (net (code "30") (name "Net-(D3-K)") (class "Default")
      (node (ref "D3") (pin "2") (pinfunction "K_2") (pintype "passive"))
      (node (ref "R3") (pin "2") (pinfunction "2_2") (pintype "passive"))
    )
    (net (code "31") (name "Net-(D4-DO)") (class "Default")
      (node (ref "D4") (pin "2") (pinfunction "DO_2") (pintype "passive"))
      (node (ref "D5") (pin "4") (pinfunction "DI_4") (pintype "passive"))
    )
    (net (code "32") (name "Net-(D5-DO)") (class "Default")
      (node (ref "D5") (pin "2") (pinfunction "DO_2") (pintype "passive"))
      (node (ref "D6") (pin "4") (pinfunction "DI_4") (pintype "passive"))
    )
    (net (code "33") (name "Net-(D6-DO)") (class "Default")
      (node (ref "D6") (pin "2") (pinfunction "DO_2") (pintype "passive"))
      (node (ref "D7") (pin "4") (pinfunction "DI_4") (pintype "passive"))
    )
    (net (code "34") (name "Net-(P1-Pad2)") (class "Default")
      (node (ref "P1") (pin "2") (pinfunction "2_2") (pintype "passive"))
      (node (ref "S1") (pin "1") (pinfunction "1_1") (pintype "passive"))
    )
    (net (code "35") (name "Net-(P2-Pad2)") (class "Default")
      (node (ref "P2") (pin "2") (pinfunction "2_2") (pintype "passive"))
      (node (ref "R1") (pin "2") (pinfunction "2_2") (pintype "passive"))
    )
    (net (code "36") (name "Net-(Q1-D)") (class "Default")
      (node (ref "C36") (pin "2") (pinfunction "2_2") (pintype "passive"))
      (node (ref "M1") (pin "2") (pinfunction "2_2") (pintype "passive"))
      (node (ref "Q1") (pin "3") (pinfunction "D_3") (pintype "passive"))
    )
    (net (code "37") (name "Net-(Q1-G)") (class "Default")
      (node (ref "Q1") (pin "1") (pinfunction "G_1") (pintype "passive"))
      (node (ref "R12") (pin "2") (pinfunction "2_2") (pintype "passive"))
      (node (ref "R13") (pin "2") (pinfunction "2_2") (pintype "passive"))
    )
    (net (code "38") (name "Net-(Q2-D)") (class "Default")
      (node (ref "C37") (pin "2") (pinfunction "2_2") (pintype "passive"))
      (node (ref "M2") (pin "2") (pinfunction "2_2") (pintype "passive"))
      (node (ref "Q2") (pin "3") (pinfunction "D_3") (pintype "passive"))
    )
    (net (code "39") (name "Net-(Q2-G)") (class "Default")
      (node (ref "Q2") (pin "1") (pinfunction "G_1") (pintype "passive"))
      (node (ref "R14") (pin "2") (pinfunction "2_2") (pintype "passive"))
      (node (ref "R15") (pin "2") (pinfunction "2_2") (pintype "passive"))
    )
    (net (code "40") (name "Net-(Q3-D)") (class "Default")
      (node (ref "C38") (pin "2") (pinfunction "2_2") (pintype "passive"))
      (node (ref "M3") (pin "2") (pinfunction "2_2") (pintype "passive"))
      (node (ref "Q3") (pin "3") (pinfunction "D_3") (pintype "passive"))
    )
    (net (code "41") (name "Net-(Q3-G)") (class "Default")
      (node (ref "Q3") (pin "1") (pinfunction "G_1") (pintype "passive"))
      (node (ref "R16") (pin "2") (pinfunction "2_2") (pintype "passive"))
      (node (ref "R17") (pin "2") (pinfunction "2_2") (pintype "passive"))
    )
    (net (code "42") (name "Net-(Q4-D)") (class "Default")
      (node (ref "C39") (pin "2") (pinfunction "2_2") (pintype "passive"))
      (node (ref "M4") (pin "2") (pinfunction "2_2") (pintype "passive"))
      (node (ref "Q4") (pin "3") (pinfunction "D_3") (pintype "passive"))
    )
    (net (code "43") (name "Net-(Q4-G)") (class "Default")
      (node (ref "Q4") (pin "1") (pinfunction "G_1") (pintype "passive"))
      (node (ref "R18") (pin "2") (pinfunction "2_2") (pintype "passive"))
      (node (ref "R19") (pin "2") (pinfunction "2_2") (pintype "passive"))
    )
    (net (code "44") (name "Net-(U1-OSC_IN{slash}PD0)") (class "Default")
      (node (ref "U1") (pin "5") (pinfunction "OSC_IN/PD0_5") (pintype "input"))
      (node (ref "Y1") (pin "3") (pinfunction "3_3") (pintype "passive"))
    )
    (net (code "45") (name "Net-(U1-OSC_OUT{slash}PD1)") (class "Default")
      (node (ref "U1") (pin "6") (pinfunction "OSC_OUT/PD1_6") (pintype "output"))
      (node (ref "Y1") (pin "1") (pinfunction "1_1") (pintype "passive"))
    )
    (net (code "46") (name "Net-(U1-PB2{slash}BOOT1)") (class "Default")
      (node (ref "R21") (pin "1") (pinfunction "1_1") (pintype "passive"))
      (node (ref "U1") (pin "20") (pinfunction "PB2/BOOT1_20") (pintype "bidirectional"))
    )
    (net (code "47") (name "Net-(U2-LX)") (class "Default")
      (node (ref "L1") (pin "2") (pinfunction "2_2") (pintype "passive"))
      (node (ref "U2") (pin "2") (pinfunction "LX_2") (pintype "passive"))
    )
    (net (code "48") (name "Net-(U4-CPOUT)") (class "Default")
      (node (ref "C32") (pin "2") (pinfunction "2_2") (pintype "passive"))
      (node (ref "U4") (pin "20") (pinfunction "CPOUT_20") (pintype "passive"))
    )
    (net (code "49") (name "Net-(U4-FSYNC)") (class "Default")
      (node (ref "R20") (pin "2") (pinfunction "2_2") (pintype "passive"))
      (node (ref "U4") (pin "11") (pinfunction "FSYNC_11") (pintype "passive"))
    )
    (net (code "50") (name "Net-(U4-REGOUT)") (class "Default")
      (node (ref "C35") (pin "1") (pinfunction "1_1") (pintype "passive"))
      (node (ref "U4") (pin "10") (pinfunction "REGOUT_10") (pintype "passive"))
    )
    (net (code "51") (name "Net-(U6-ANT1)") (class "Default")
      (node (ref "L2") (pin "2") (pinfunction "2_2") (pintype "passive"))
      (node (ref "L3") (pin "2") (pinfunction "2_2") (pintype "passive"))
      (node (ref "U6") (pin "12") (pinfunction "ANT1_12") (pintype "passive"))
    )
    (net (code "52") (name "Net-(U6-ANT2)") (class "Default")
      (node (ref "L2") (pin "1") (pinfunction "1_1") (pintype "passive"))
      (node (ref "L4") (pin "1") (pinfunction "1_1") (pintype "passive"))
      (node (ref "U6") (pin "13") (pinfunction "ANT2_13") (pintype "passive"))
    )
    (net (code "53") (name "Net-(U6-DVDD)") (class "Default")
      (node (ref "C24") (pin "1") (pinfunction "1_1") (pintype "passive"))
      (node (ref "U6") (pin "19") (pinfunction "DVDD_19") (pintype "passive"))
    )
    (net (code "54") (name "Net-(U6-IREF)") (class "Default")
      (node (ref "R22") (pin "2") (pinfunction "2_2") (pintype "passive"))
      (node (ref "U6") (pin "16") (pinfunction "IREF_16") (pintype "passive"))
    )
    (net (code "55") (name "Net-(U6-VDD_PA)") (class "Default")
      (node (ref "C26") (pin "1") (pinfunction "1_1") (pintype "passive"))
      (node (ref "C27") (pin "1") (pinfunction "1_1") (pintype "passive"))
      (node (ref "L3") (pin "1") (pinfunction "1_1") (pintype "passive"))
      (node (ref "U6") (pin "11") (pinfunction "VDD_PA_11") (pintype "passive"))
    )
    (net (code "56") (name "Net-(U6-XC1)") (class "Default")
      (node (ref "C30") (pin "2") (pinfunction "2_2") (pintype "passive"))
      (node (ref "U6") (pin "10") (pinfunction "XC1_10") (pintype "passive"))
      (node (ref "X2") (pin "3") (pinfunction "3_3") (pintype "passive"))
    )
    (net (code "57") (name "Net-(U6-XC2)") (class "Default")
      (node (ref "C29") (pin "2") (pinfunction "2_2") (pintype "passive"))
      (node (ref "U6") (pin "9") (pinfunction "XC2_9") (pintype "passive"))
      (node (ref "X2") (pin "1") (pinfunction "1_1") (pintype "passive"))
    )
    (net (code "58") (name "RF_3.3V") (class "Default")
      (node (ref "C22") (pin "2") (pinfunction "2_2") (pintype "passive"))
      (node (ref "C23") (pin "2") (pinfunction "2_2") (pintype "passive"))
      (node (ref "R9") (pin "1") (pinfunction "1_1") (pintype "passive"))
      (node (ref "U6") (pin "15") (pinfunction "VDD_15") (pintype "passive"))
      (node (ref "U6") (pin "18") (pinfunction "VDD_18") (pintype "passive"))
      (node (ref "U6") (pin "7") (pinfunction "VDD_7") (pintype "passive"))
    )
    (net (code "59") (name "RF_GND") (class "Default")
      (node (ref "C22") (pin "1") (pinfunction "1_1") (pintype "passive"))
      (node (ref "C23") (pin "1") (pinfunction "1_1") (pintype "passive"))
      (node (ref "C24") (pin "2") (pinfunction "2_2") (pintype "passive"))
      (node (ref "C26") (pin "2") (pinfunction "2_2") (pintype "passive"))
      (node (ref "C27") (pin "2") (pinfunction "2_2") (pintype "passive"))
      (node (ref "C28") (pin "1") (pinfunction "1_1") (pintype "passive"))
      (node (ref "C29") (pin "1") (pinfunction "1_1") (pintype "passive"))
      (node (ref "C30") (pin "1") (pinfunction "1_1") (pintype "passive"))
      (node (ref "R22") (pin "1") (pinfunction "1_1") (pintype "passive"))
      (node (ref "R8") (pin "1") (pinfunction "1_1") (pintype "passive"))
      (node (ref "U6") (pin "14") (pinfunction "VSS_14") (pintype "passive"))
      (node (ref "U6") (pin "17") (pinfunction "VSS_17") (pintype "passive"))
      (node (ref "U6") (pin "20") (pinfunction "VSS_20") (pintype "passive"))
      (node (ref "U6") (pin "8") (pinfunction "VSS_8") (pintype "passive"))
    )
    (net (code "60") (name "VBAT") (class "Default")
      (node (ref "C1") (pin "2") (pinfunction "2_2") (pintype "passive"))
      (node (ref "C36") (pin "1") (pinfunction "1_1") (pintype "passive"))
      (node (ref "C37") (pin "1") (pinfunction "1_1") (pintype "passive"))
      (node (ref "C38") (pin "1") (pinfunction "1_1") (pintype "passive"))
      (node (ref "C39") (pin "1") (pinfunction "1_1") (pintype "passive"))
      (node (ref "L1") (pin "1") (pinfunction "1_1") (pintype "passive"))
      (node (ref "M1") (pin "1") (pinfunction "1_1") (pintype "passive"))
      (node (ref "M2") (pin "1") (pinfunction "1_1") (pintype "passive"))
      (node (ref "M3") (pin "1") (pinfunction "1_1") (pintype "passive"))
      (node (ref "M4") (pin "1") (pinfunction "1_1") (pintype "passive"))
      (node (ref "R6") (pin "1") (pinfunction "1_1") (pintype "passive"))
      (node (ref "S1") (pin "2") (pinfunction "2_2") (pintype "passive"))
    )
    (net (code "61") (name "unconnected-(D7-DO-Pad2)") (class "Default")
      (node (ref "D7") (pin "2") (pinfunction "DO_2") (pintype "passive"))
    )
    (net (code "62") (name "unconnected-(S1-Pad3)") (class "Default")
      (node (ref "S1") (pin "3") (pinfunction "3_3") (pintype "passive+no_connect"))
    )
    (net (code "63") (name "unconnected-(U1-PA0-WKUP-Pad10)") (class "Default")
      (node (ref "U1") (pin "10") (pinfunction "PA0-WKUP_10") (pintype "bidirectional"))
    )
    (net (code "64") (name "unconnected-(U1-PA2-Pad12)") (class "Default")
      (node (ref "U1") (pin "12") (pinfunction "PA2_12") (pintype "bidirectional"))
    )
    (net (code "65") (name "unconnected-(U1-PA3-Pad13)") (class "Default")
      (node (ref "U1") (pin "13") (pinfunction "PA3_13") (pintype "bidirectional"))
    )
    (net (code "66") (name "unconnected-(U1-PA4-Pad14)") (class "Default")
      (node (ref "U1") (pin "14") (pinfunction "PA4_14") (pintype "bidirectional"))
    )
    (net (code "67") (name "unconnected-(U1-PA5-Pad15)") (class "Default")
      (node (ref "U1") (pin "15") (pinfunction "PA5_15") (pintype "bidirectional"))
    )
    (net (code "68") (name "unconnected-(U1-PA8-Pad29)") (class "Default")
      (node (ref "U1") (pin "29") (pinfunction "PA8_29") (pintype "bidirectional"))
    )
    (net (code "69") (name "unconnected-(U1-PA15{slash}JTDI-Pad38)") (class "Default")
      (node (ref "U1") (pin "38") (pinfunction "PA15/JTDI_38") (pintype "bidirectional"))
    )
    (net (code "70") (name "unconnected-(U1-PB4{slash}JNTRST-Pad40)") (class "Default")
      (node (ref "U1") (pin "40") (pinfunction "PB4/JNTRST_40") (pintype "bidirectional"))
    )
    (net (code "71") (name "unconnected-(U1-PB9-Pad46)") (class "Default")
      (node (ref "U1") (pin "46") (pinfunction "PB9_46") (pintype "bidirectional"))
    )
    (net (code "72") (name "unconnected-(U1-PB10-Pad21)") (class "Default")
      (node (ref "U1") (pin "21") (pinfunction "PB10_21") (pintype "bidirectional"))
    )
    (net (code "73") (name "unconnected-(U1-PB11-Pad22)") (class "Default")
      (node (ref "U1") (pin "22") (pinfunction "PB11_22") (pintype "bidirectional"))
    )
    (net (code "74") (name "unconnected-(U1-PC13-TAMPER-RTC-Pad2)") (class "Default")
      (node (ref "U1") (pin "2") (pinfunction "PC13-TAMPER-RTC_2") (pintype "bidirectional"))
    )
    (net (code "75") (name "unconnected-(U1-PC14-OSC32_IN-Pad3)") (class "Default")
      (node (ref "U1") (pin "3") (pinfunction "PC14-OSC32_IN_3") (pintype "bidirectional"))
    )
    (net (code "76") (name "unconnected-(U1-PC15-OSC32_OUT-Pad4)") (class "Default")
      (node (ref "U1") (pin "4") (pinfunction "PC15-OSC32_OUT_4") (pintype "bidirectional"))
    )
    (net (code "77") (name "unconnected-(U4-A-CL-Pad7)") (class "Default")
      (node (ref "U4") (pin "7") (pinfunction "A-CL_7") (pintype "passive+no_connect"))
    )
    (net (code "78") (name "unconnected-(U4-A_DA-Pad6)") (class "Default")
      (node (ref "U4") (pin "6") (pinfunction "A_DA_6") (pintype "passive+no_connect"))
    )
    (net (code "79") (name "unconnected-(U4-CLKOUT-Pad22)") (class "Default")
      (node (ref "U4") (pin "22") (pinfunction "CLKOUT_22") (pintype "passive+no_connect"))
    )
    (net (code "80") (name "unconnected-(U4-NC-Pad2)") (class "Default")
      (node (ref "U4") (pin "2") (pinfunction "NC_2") (pintype "passive+no_connect"))
    )
    (net (code "81") (name "unconnected-(U4-NC-Pad3)") (class "Default")
      (node (ref "U4") (pin "3") (pinfunction "NC_3") (pintype "passive+no_connect"))
    )
    (net (code "82") (name "unconnected-(U4-NC-Pad4)") (class "Default")
      (node (ref "U4") (pin "4") (pinfunction "NC_4") (pintype "passive+no_connect"))
    )
    (net (code "83") (name "unconnected-(U4-NC-Pad5)") (class "Default")
      (node (ref "U4") (pin "5") (pinfunction "NC_5") (pintype "passive+no_connect"))
    )
    (net (code "84") (name "unconnected-(U4-NC-Pad14)") (class "Default")
      (node (ref "U4") (pin "14") (pinfunction "NC_14") (pintype "passive+no_connect"))
    )
    (net (code "85") (name "unconnected-(U4-NC-Pad15)") (class "Default")
      (node (ref "U4") (pin "15") (pinfunction "NC_15") (pintype "passive+no_connect"))
    )
    (net (code "86") (name "unconnected-(U4-NC-Pad16)") (class "Default")
      (node (ref "U4") (pin "16") (pinfunction "NC_16") (pintype "passive+no_connect"))
    )
    (net (code "87") (name "unconnected-(U4-NC-Pad17)") (class "Default")
      (node (ref "U4") (pin "17") (pinfunction "NC_17") (pintype "passive+no_connect"))
    )
    (net (code "88") (name "unconnected-(U4-RESV-Pad19)") (class "Default")
      (node (ref "U4") (pin "19") (pinfunction "RESV_19") (pintype "passive+no_connect"))
    )
    (net (code "89") (name "unconnected-(U4-RESV-Pad21)") (class "Default")
      (node (ref "U4") (pin "21") (pinfunction "RESV_21") (pintype "passive+no_connect"))
    )
    (net (code "90") (name "unconnected-(X2-GND-Pad2)") (class "Default")
      (node (ref "X2") (pin "2") (pinfunction "GND_2") (pintype "passive+no_connect"))
    )
    (net (code "91") (name "unconnected-(X2-GND-Pad4)") (class "Default")
      (node (ref "X2") (pin "4") (pinfunction "GND_4") (pintype "passive+no_connect"))
    )
  )
)
